# Pixel1_0_2.net
KiCad netlist of a schematic drawn in Altium Designer
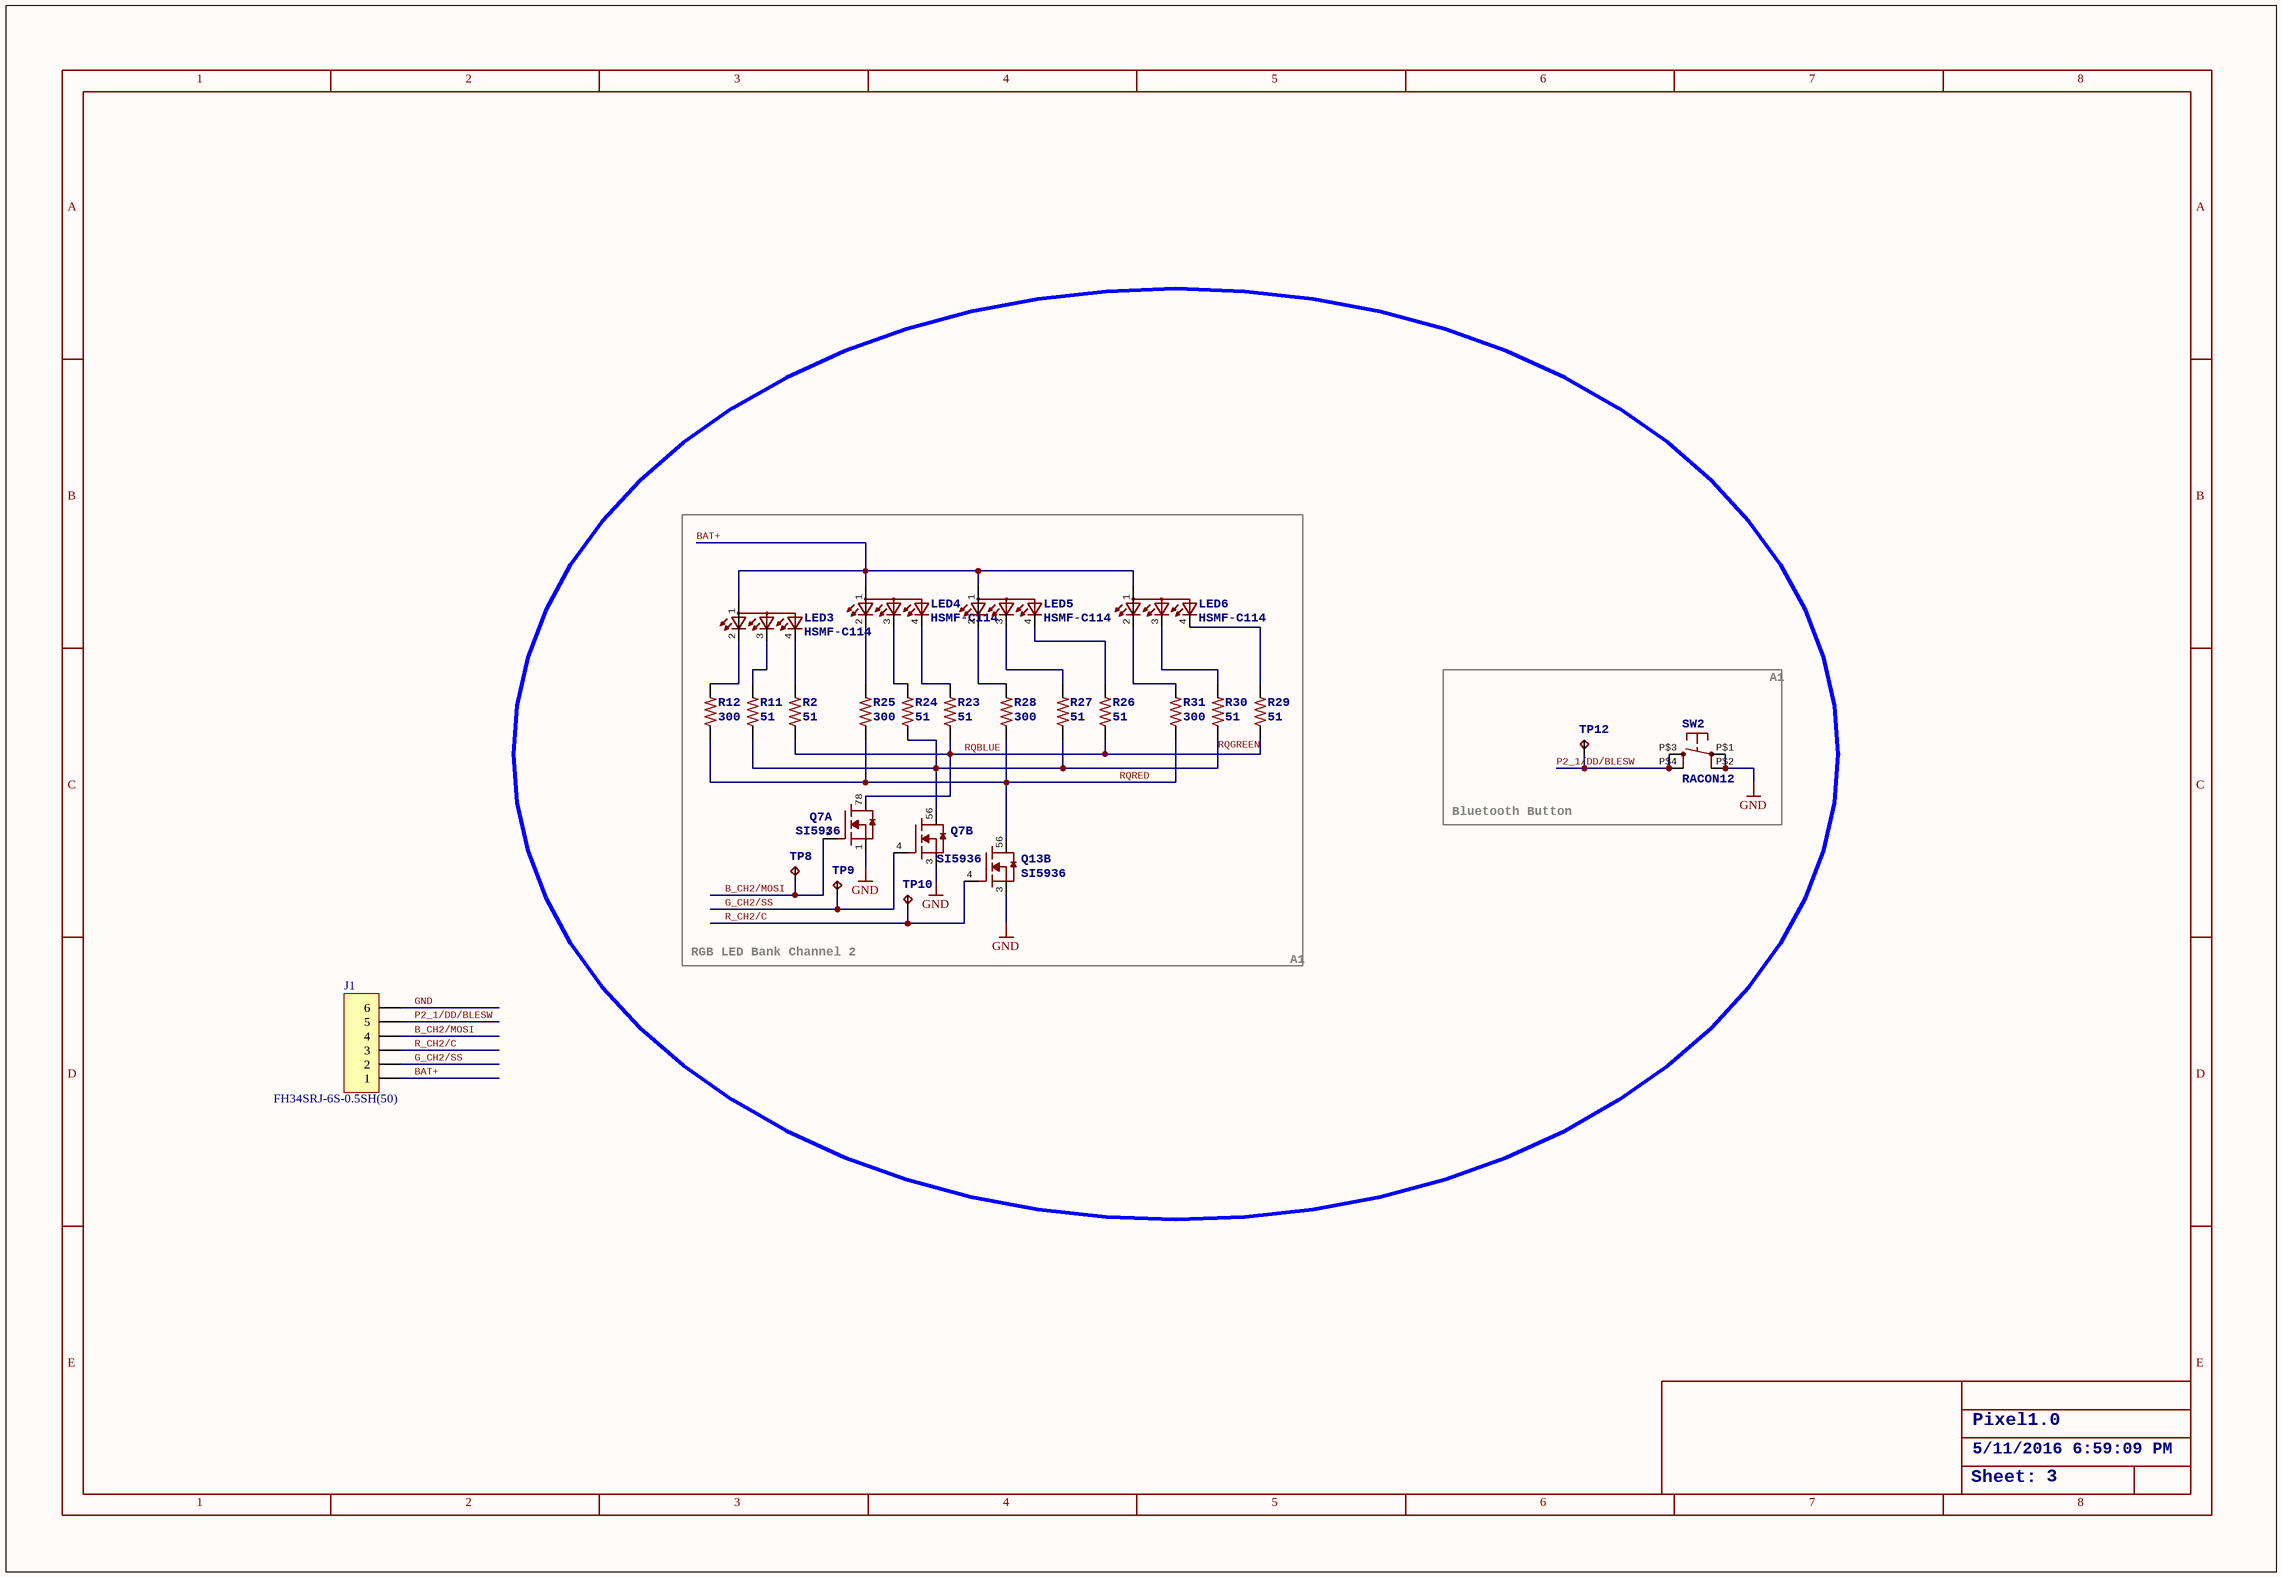
[diagram p0: Pixel1.0_2.SchDoc]

(export (version "E")
  (design (tool "Eeschema 10.0.6"))
  (components
    (comp (ref "J1")
      (value "FH34SRJ-6S-0.5SH(50)")
      (footprint "59453061110ECHLF")
      (description "WR-FPC 0.50mm SMT ZIF Horizontal Bottom Contact")
      (fields
        (field (name "MANUFACTURER") "Würth Elektronik eiSos GmbH")
        (field (name "PARTNO") "68710614522")
        (field (name "CREATED BY") "Karrer Zheng")
      )
      (libsource (lib "Components") (part "WE-ZIF Connector WR-FPC 68710614522"))
    )
    (comp (ref "LED3")
      (value "HSMF-C114")
      (footprint "HSMFC114")
      (description "Chip LED RGB   Source: http://document.sharpsma.com/files/GM1WA55311A_SS.pdf")
      (libsource (lib "vapeix") (part "HSMF-C114"))
    )
    (comp (ref "LED4")
      (value "HSMF-C114")
      (footprint "HSMFC114")
      (description "Chip LED RGB   Source: http://document.sharpsma.com/files/GM1WA55311A_SS.pdf")
      (libsource (lib "vapeix") (part "HSMF-C114"))
    )
    (comp (ref "LED5")
      (value "HSMF-C114")
      (footprint "HSMFC114")
      (description "Chip LED RGB   Source: http://document.sharpsma.com/files/GM1WA55311A_SS.pdf")
      (libsource (lib "vapeix") (part "HSMF-C114"))
    )
    (comp (ref "LED6")
      (value "HSMF-C114")
      (footprint "HSMFC114")
      (description "Chip LED RGB   Source: http://document.sharpsma.com/files/GM1WA55311A_SS.pdf")
      (libsource (lib "vapeix") (part "HSMF-C114"))
    )
    (comp (ref "Q7")
      (value "SI5936")
      (footprint "1206-8CHIP-FET")
      (libsource (lib "Pixel1.0") (part "SI5936"))
    )
    (comp (ref "Q13")
      (value "SI5936")
      (footprint "1206-8CHIP-FET")
      (libsource (lib "Pixel1.0") (part "SI5936"))
    )
    (comp (ref "R2")
      (value "51")
      (footprint "R0201")
      (description "RESISTOR, American symbol")
      (libsource (lib "rcl") (part "R-US_R0201"))
    )
    (comp (ref "R11")
      (value "51")
      (footprint "R0201")
      (description "RESISTOR, American symbol")
      (libsource (lib "rcl") (part "R-US_R0201"))
    )
    (comp (ref "R12")
      (value "300")
      (footprint "R0201")
      (description "RESISTOR, American symbol")
      (libsource (lib "rcl") (part "R-US_R0201"))
    )
    (comp (ref "R23")
      (value "51")
      (footprint "R0201")
      (description "RESISTOR, American symbol")
      (libsource (lib "rcl") (part "R-US_R0201"))
    )
    (comp (ref "R24")
      (value "51")
      (footprint "R0201")
      (description "RESISTOR, American symbol")
      (libsource (lib "rcl") (part "R-US_R0201"))
    )
    (comp (ref "R25")
      (value "300")
      (footprint "R0201")
      (description "RESISTOR, American symbol")
      (libsource (lib "rcl") (part "R-US_R0201"))
    )
    (comp (ref "R26")
      (value "51")
      (footprint "R0201")
      (description "RESISTOR, American symbol")
      (libsource (lib "rcl") (part "R-US_R0201"))
    )
    (comp (ref "R27")
      (value "51")
      (footprint "R0201")
      (description "RESISTOR, American symbol")
      (libsource (lib "rcl") (part "R-US_R0201"))
    )
    (comp (ref "R28")
      (value "300")
      (footprint "R0201")
      (description "RESISTOR, American symbol")
      (libsource (lib "rcl") (part "R-US_R0201"))
    )
    (comp (ref "R29")
      (value "51")
      (footprint "R0201")
      (description "RESISTOR, American symbol")
      (libsource (lib "rcl") (part "R-US_R0201"))
    )
    (comp (ref "R30")
      (value "51")
      (footprint "R0201")
      (description "RESISTOR, American symbol")
      (libsource (lib "rcl") (part "R-US_R0201"))
    )
    (comp (ref "R31")
      (value "300")
      (footprint "R0201")
      (description "RESISTOR, American symbol")
      (libsource (lib "rcl") (part "R-US_R0201"))
    )
    (comp (ref "SW2")
      (value "RACON12")
      (footprint "RACON12")
      (description "ITT SWITCH")
      (libsource (lib "vapeix") (part "RACON12"))
    )
    (comp (ref "TP8")
      (value "TPTP06R")
      (footprint "TP06R")
      (description "Test pad")
      (libsource (lib "testpad") (part "TPTP06R"))
    )
    (comp (ref "TP9")
      (value "TPTP06R")
      (footprint "TP06R")
      (description "Test pad")
      (libsource (lib "testpad") (part "TPTP06R"))
    )
    (comp (ref "TP10")
      (value "TPTP06R")
      (footprint "TP06R")
      (description "Test pad")
      (libsource (lib "testpad") (part "TPTP06R"))
    )
    (comp (ref "TP12")
      (value "TPTP06R")
      (footprint "TP06R")
      (description "Test pad")
      (libsource (lib "testpad") (part "TPTP06R"))
    )
  )
  (nets
    (net (code "1") (name "/BAT+") (class "Default")
      (node (ref "J1") (pin "1") (pinfunction "1_1") (pintype "passive"))
      (node (ref "LED3") (pin "1") (pinfunction "A_1") (pintype "passive"))
      (node (ref "LED4") (pin "1") (pinfunction "A_1") (pintype "passive"))
      (node (ref "LED5") (pin "1") (pinfunction "A_1") (pintype "passive"))
      (node (ref "LED6") (pin "1") (pinfunction "A_1") (pintype "passive"))
    )
    (net (code "2") (name "/B_CH2{slash}MOSI") (class "Default")
      (node (ref "J1") (pin "4") (pinfunction "4_4") (pintype "passive"))
      (node (ref "Q7") (pin "2") (pinfunction "G1_2") (pintype "passive"))
      (node (ref "TP8") (pin "TP") (pinfunction "TP_TP") (pintype "passive"))
    )
    (net (code "3") (name "/G_CH2{slash}SS") (class "Default")
      (node (ref "J1") (pin "2") (pinfunction "2_2") (pintype "passive"))
      (node (ref "Q7") (pin "4") (pinfunction "G2_4") (pintype "passive"))
      (node (ref "TP9") (pin "TP") (pinfunction "TP_TP") (pintype "passive"))
    )
    (net (code "4") (name "/P2_1{slash}DD{slash}BLESW") (class "Default")
      (node (ref "J1") (pin "5") (pinfunction "5_5") (pintype "passive"))
      (node (ref "SW2") (pin "P$3") (pinfunction "S_P$3") (pintype "passive"))
      (node (ref "SW2") (pin "P$4") (pinfunction "S_P$4") (pintype "passive"))
      (node (ref "TP12") (pin "TP") (pinfunction "TP_TP") (pintype "passive"))
    )
    (net (code "5") (name "/RQBLUE") (class "Default")
      (node (ref "Q7") (pin "78") (pinfunction "D1_78") (pintype "passive"))
      (node (ref "R2") (pin "1") (pinfunction "1_1") (pintype "passive"))
      (node (ref "R23") (pin "1") (pinfunction "1_1") (pintype "passive"))
      (node (ref "R26") (pin "1") (pinfunction "1_1") (pintype "passive"))
      (node (ref "R29") (pin "1") (pinfunction "1_1") (pintype "passive"))
    )
    (net (code "6") (name "/RQGREEN") (class "Default")
      (node (ref "Q7") (pin "56") (pinfunction "D2_56") (pintype "passive"))
      (node (ref "R11") (pin "1") (pinfunction "1_1") (pintype "passive"))
      (node (ref "R24") (pin "1") (pinfunction "1_1") (pintype "passive"))
      (node (ref "R27") (pin "1") (pinfunction "1_1") (pintype "passive"))
      (node (ref "R30") (pin "1") (pinfunction "1_1") (pintype "passive"))
    )
    (net (code "7") (name "/RQRED") (class "Default")
      (node (ref "Q13") (pin "56") (pinfunction "D2_56") (pintype "passive"))
      (node (ref "R12") (pin "1") (pinfunction "1_1") (pintype "passive"))
      (node (ref "R25") (pin "1") (pinfunction "1_1") (pintype "passive"))
      (node (ref "R28") (pin "1") (pinfunction "1_1") (pintype "passive"))
      (node (ref "R31") (pin "1") (pinfunction "1_1") (pintype "passive"))
    )
    (net (code "8") (name "/R_CH2{slash}C") (class "Default")
      (node (ref "J1") (pin "3") (pinfunction "3_3") (pintype "passive"))
      (node (ref "Q13") (pin "4") (pinfunction "G2_4") (pintype "passive"))
      (node (ref "TP10") (pin "TP") (pinfunction "TP_TP") (pintype "passive"))
    )
    (net (code "9") (name "GND") (class "Default")
      (node (ref "J1") (pin "6") (pinfunction "6_6") (pintype "passive"))
      (node (ref "Q13") (pin "3") (pinfunction "S2_3") (pintype "passive"))
      (node (ref "Q7") (pin "1") (pinfunction "S1_1") (pintype "passive"))
      (node (ref "Q7") (pin "3") (pinfunction "S2_3") (pintype "passive"))
      (node (ref "SW2") (pin "P$1") (pinfunction "P_P$1") (pintype "passive"))
      (node (ref "SW2") (pin "P$2") (pinfunction "P_P$2") (pintype "passive"))
    )
    (net (code "10") (name "Net-(LED3-BLUE)") (class "Default")
      (node (ref "LED3") (pin "4") (pinfunction "BLUE_4") (pintype "passive"))
      (node (ref "R2") (pin "2") (pinfunction "2_2") (pintype "passive"))
    )
    (net (code "11") (name "Net-(LED3-GREEN)") (class "Default")
      (node (ref "LED3") (pin "3") (pinfunction "GREEN_3") (pintype "passive"))
      (node (ref "R11") (pin "2") (pinfunction "2_2") (pintype "passive"))
    )
    (net (code "12") (name "Net-(LED3-RED)") (class "Default")
      (node (ref "LED3") (pin "2") (pinfunction "RED_2") (pintype "passive"))
      (node (ref "R12") (pin "2") (pinfunction "2_2") (pintype "passive"))
    )
    (net (code "13") (name "Net-(LED4-BLUE)") (class "Default")
      (node (ref "LED4") (pin "4") (pinfunction "BLUE_4") (pintype "passive"))
      (node (ref "R23") (pin "2") (pinfunction "2_2") (pintype "passive"))
    )
    (net (code "14") (name "Net-(LED4-GREEN)") (class "Default")
      (node (ref "LED4") (pin "3") (pinfunction "GREEN_3") (pintype "passive"))
      (node (ref "R24") (pin "2") (pinfunction "2_2") (pintype "passive"))
    )
    (net (code "15") (name "Net-(LED4-RED)") (class "Default")
      (node (ref "LED4") (pin "2") (pinfunction "RED_2") (pintype "passive"))
      (node (ref "R25") (pin "2") (pinfunction "2_2") (pintype "passive"))
    )
    (net (code "16") (name "Net-(LED5-BLUE)") (class "Default")
      (node (ref "LED5") (pin "4") (pinfunction "BLUE_4") (pintype "passive"))
      (node (ref "R26") (pin "2") (pinfunction "2_2") (pintype "passive"))
    )
    (net (code "17") (name "Net-(LED5-GREEN)") (class "Default")
      (node (ref "LED5") (pin "3") (pinfunction "GREEN_3") (pintype "passive"))
      (node (ref "R27") (pin "2") (pinfunction "2_2") (pintype "passive"))
    )
    (net (code "18") (name "Net-(LED5-RED)") (class "Default")
      (node (ref "LED5") (pin "2") (pinfunction "RED_2") (pintype "passive"))
      (node (ref "R28") (pin "2") (pinfunction "2_2") (pintype "passive"))
    )
    (net (code "19") (name "Net-(LED6-BLUE)") (class "Default")
      (node (ref "LED6") (pin "4") (pinfunction "BLUE_4") (pintype "passive"))
      (node (ref "R29") (pin "2") (pinfunction "2_2") (pintype "passive"))
    )
    (net (code "20") (name "Net-(LED6-GREEN)") (class "Default")
      (node (ref "LED6") (pin "3") (pinfunction "GREEN_3") (pintype "passive"))
      (node (ref "R30") (pin "2") (pinfunction "2_2") (pintype "passive"))
    )
    (net (code "21") (name "Net-(LED6-RED)") (class "Default")
      (node (ref "LED6") (pin "2") (pinfunction "RED_2") (pintype "passive"))
      (node (ref "R31") (pin "2") (pinfunction "2_2") (pintype "passive"))
    )
  )
)
